# cek_pin_37.net
KiCad netlist of a schematic drawn in EAGLE
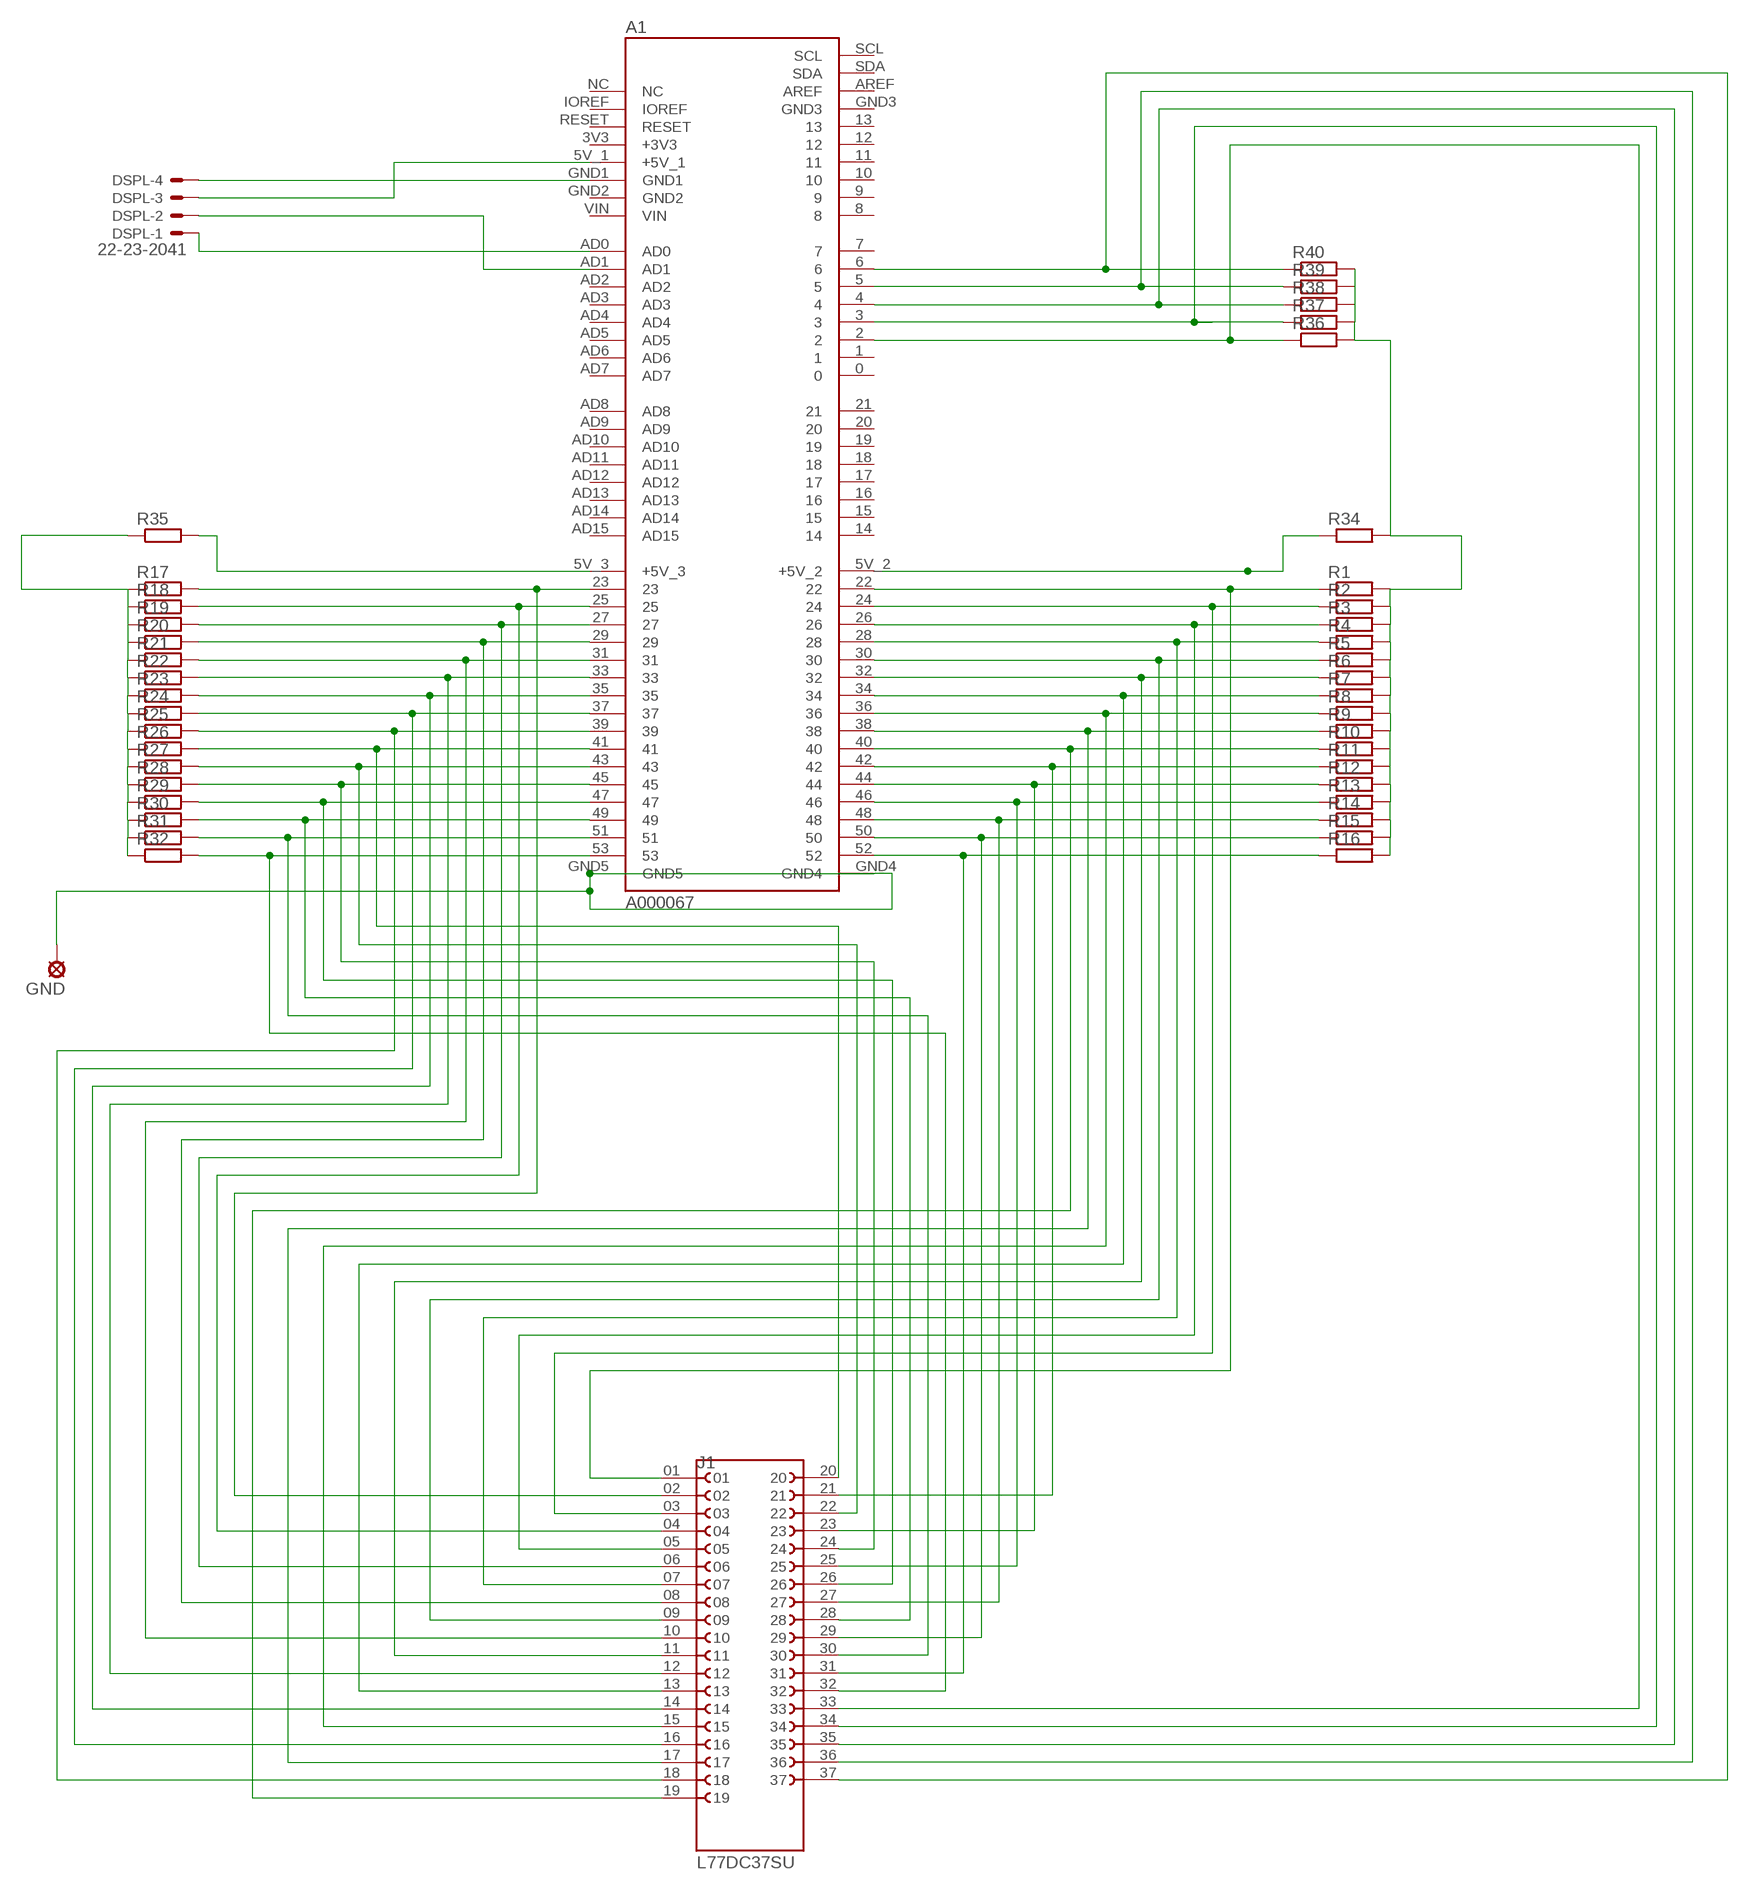
[diagram p0: schematic, sheet 1]

(export (version "E")
  (design (tool "Eeschema 10.0.6"))
  (components
    (comp (ref "A1")
      (value "A000067")
      (footprint "eagle-import:ARDUINO_A000067")
      (fields (field (name "MF") "Arduino") (field (name "MP") "Arduino Mega 2560 Rev3"))
      (libsource (lib "eagle-import") (part "A000067"))
    )
    (comp (ref "DSPL")
      (value "22-23-2041")
      (footprint "eagle-import:22-23-2041")
      (fields (field (name "MF") "MOLEX"))
      (libsource (lib "eagle-import") (part "22-23-2041"))
    )
    (comp (ref "GND")
      (value "LSP10")
      (footprint "eagle-import:LSP10")
      (libsource (lib "eagle-import") (part "LSP10"))
    )
    (comp (ref "J1")
      (value "L77DC37SU")
      (footprint "eagle-import:AMPHENOL_L77DC37SU")
      (fields (field (name "MF") "Amphenol Commercial Products") (field (name "MP") "L77-DC37S-U"))
      (libsource (lib "eagle-import") (part "L77DC37SU"))
    )
    (comp (ref "R1")
      (value "R-EU_0207/12")
      (footprint "eagle-import:0207_12")
      (libsource (lib "eagle-import") (part "R-EU_0207/12"))
    )
    (comp (ref "R2")
      (value "R-EU_0207/12")
      (footprint "eagle-import:0207_12")
      (libsource (lib "eagle-import") (part "R-EU_0207/12"))
    )
    (comp (ref "R3")
      (value "R-EU_0207/12")
      (footprint "eagle-import:0207_12")
      (libsource (lib "eagle-import") (part "R-EU_0207/12"))
    )
    (comp (ref "R4")
      (value "R-EU_0207/12")
      (footprint "eagle-import:0207_12")
      (libsource (lib "eagle-import") (part "R-EU_0207/12"))
    )
    (comp (ref "R5")
      (value "R-EU_0207/12")
      (footprint "eagle-import:0207_12")
      (libsource (lib "eagle-import") (part "R-EU_0207/12"))
    )
    (comp (ref "R6")
      (value "R-EU_0207/12")
      (footprint "eagle-import:0207_12")
      (libsource (lib "eagle-import") (part "R-EU_0207/12"))
    )
    (comp (ref "R7")
      (value "R-EU_0207/12")
      (footprint "eagle-import:0207_12")
      (libsource (lib "eagle-import") (part "R-EU_0207/12"))
    )
    (comp (ref "R8")
      (value "R-EU_0207/12")
      (footprint "eagle-import:0207_12")
      (libsource (lib "eagle-import") (part "R-EU_0207/12"))
    )
    (comp (ref "R9")
      (value "R-EU_0207/12")
      (footprint "eagle-import:0207_12")
      (libsource (lib "eagle-import") (part "R-EU_0207/12"))
    )
    (comp (ref "R10")
      (value "R-EU_0207/12")
      (footprint "eagle-import:0207_12")
      (libsource (lib "eagle-import") (part "R-EU_0207/12"))
    )
    (comp (ref "R11")
      (value "R-EU_0207/12")
      (footprint "eagle-import:0207_12")
      (libsource (lib "eagle-import") (part "R-EU_0207/12"))
    )
    (comp (ref "R12")
      (value "R-EU_0207/12")
      (footprint "eagle-import:0207_12")
      (libsource (lib "eagle-import") (part "R-EU_0207/12"))
    )
    (comp (ref "R13")
      (value "R-EU_0207/12")
      (footprint "eagle-import:0207_12")
      (libsource (lib "eagle-import") (part "R-EU_0207/12"))
    )
    (comp (ref "R14")
      (value "R-EU_0207/12")
      (footprint "eagle-import:0207_12")
      (libsource (lib "eagle-import") (part "R-EU_0207/12"))
    )
    (comp (ref "R15")
      (value "R-EU_0207/12")
      (footprint "eagle-import:0207_12")
      (libsource (lib "eagle-import") (part "R-EU_0207/12"))
    )
    (comp (ref "R16")
      (value "R-EU_0207/12")
      (footprint "eagle-import:0207_12")
      (libsource (lib "eagle-import") (part "R-EU_0207/12"))
    )
    (comp (ref "R17")
      (value "R-EU_0207/12")
      (footprint "eagle-import:0207_12")
      (libsource (lib "eagle-import") (part "R-EU_0207/12"))
    )
    (comp (ref "R18")
      (value "R-EU_0207/12")
      (footprint "eagle-import:0207_12")
      (libsource (lib "eagle-import") (part "R-EU_0207/12"))
    )
    (comp (ref "R19")
      (value "R-EU_0207/12")
      (footprint "eagle-import:0207_12")
      (libsource (lib "eagle-import") (part "R-EU_0207/12"))
    )
    (comp (ref "R20")
      (value "R-EU_0207/12")
      (footprint "eagle-import:0207_12")
      (libsource (lib "eagle-import") (part "R-EU_0207/12"))
    )
    (comp (ref "R21")
      (value "R-EU_0207/12")
      (footprint "eagle-import:0207_12")
      (libsource (lib "eagle-import") (part "R-EU_0207/12"))
    )
    (comp (ref "R22")
      (value "R-EU_0207/12")
      (footprint "eagle-import:0207_12")
      (libsource (lib "eagle-import") (part "R-EU_0207/12"))
    )
    (comp (ref "R23")
      (value "R-EU_0207/12")
      (footprint "eagle-import:0207_12")
      (libsource (lib "eagle-import") (part "R-EU_0207/12"))
    )
    (comp (ref "R24")
      (value "R-EU_0207/12")
      (footprint "eagle-import:0207_12")
      (libsource (lib "eagle-import") (part "R-EU_0207/12"))
    )
    (comp (ref "R25")
      (value "R-EU_0207/12")
      (footprint "eagle-import:0207_12")
      (libsource (lib "eagle-import") (part "R-EU_0207/12"))
    )
    (comp (ref "R26")
      (value "R-EU_0207/12")
      (footprint "eagle-import:0207_12")
      (libsource (lib "eagle-import") (part "R-EU_0207/12"))
    )
    (comp (ref "R27")
      (value "R-EU_0207/12")
      (footprint "eagle-import:0207_12")
      (libsource (lib "eagle-import") (part "R-EU_0207/12"))
    )
    (comp (ref "R28")
      (value "R-EU_0207/12")
      (footprint "eagle-import:0207_12")
      (libsource (lib "eagle-import") (part "R-EU_0207/12"))
    )
    (comp (ref "R29")
      (value "R-EU_0207/12")
      (footprint "eagle-import:0207_12")
      (libsource (lib "eagle-import") (part "R-EU_0207/12"))
    )
    (comp (ref "R30")
      (value "R-EU_0207/12")
      (footprint "eagle-import:0207_12")
      (libsource (lib "eagle-import") (part "R-EU_0207/12"))
    )
    (comp (ref "R31")
      (value "R-EU_0207/12")
      (footprint "eagle-import:0207_12")
      (libsource (lib "eagle-import") (part "R-EU_0207/12"))
    )
    (comp (ref "R32")
      (value "R-EU_0207/12")
      (footprint "eagle-import:0207_12")
      (libsource (lib "eagle-import") (part "R-EU_0207/12"))
    )
    (comp (ref "R34")
      (value "R-EU_0207/12")
      (footprint "eagle-import:0207_12")
      (libsource (lib "eagle-import") (part "R-EU_0207/12"))
    )
    (comp (ref "R35")
      (value "R-EU_0207/12")
      (footprint "eagle-import:0207_12")
      (libsource (lib "eagle-import") (part "R-EU_0207/12"))
    )
    (comp (ref "R36")
      (value "R-EU_0207/12")
      (footprint "eagle-import:0207_12")
      (libsource (lib "eagle-import") (part "R-EU_0207/12"))
    )
    (comp (ref "R37")
      (value "R-EU_0207/12")
      (footprint "eagle-import:0207_12")
      (libsource (lib "eagle-import") (part "R-EU_0207/12"))
    )
    (comp (ref "R38")
      (value "R-EU_0207/12")
      (footprint "eagle-import:0207_12")
      (libsource (lib "eagle-import") (part "R-EU_0207/12"))
    )
    (comp (ref "R39")
      (value "R-EU_0207/12")
      (footprint "eagle-import:0207_12")
      (libsource (lib "eagle-import") (part "R-EU_0207/12"))
    )
    (comp (ref "R40")
      (value "R-EU_0207/12")
      (footprint "eagle-import:0207_12")
      (libsource (lib "eagle-import") (part "R-EU_0207/12"))
    )
  )
  (nets
    (net (code "1") (name "Net-(A1-+5V_1)") (class "Default")
      (node (ref "A1") (pin "5V_1") (pinfunction "+5V_1_5V_1") (pintype "passive"))
      (node (ref "DSPL") (pin "3") (pinfunction "S_3") (pintype "passive"))
    )
    (net (code "2") (name "Net-(A1-+5V_2)") (class "Default")
      (node (ref "A1") (pin "5V_2") (pinfunction "+5V_2_5V_2") (pintype "passive"))
      (node (ref "R34") (pin "1") (pinfunction "1_1") (pintype "passive"))
    )
    (net (code "3") (name "Net-(A1-+5V_3)") (class "Default")
      (node (ref "A1") (pin "5V_3") (pinfunction "+5V_3_5V_3") (pintype "passive"))
      (node (ref "R35") (pin "2") (pinfunction "2_2") (pintype "passive"))
    )
    (net (code "4") (name "Net-(A1-Pad2)") (class "Default")
      (node (ref "A1") (pin "2") (pinfunction "2_2") (pintype "passive"))
      (node (ref "J1") (pin "33") (pinfunction "33_33") (pintype "passive"))
      (node (ref "R36") (pin "1") (pinfunction "1_1") (pintype "passive"))
    )
    (net (code "5") (name "Net-(A1-Pad3)") (class "Default")
      (node (ref "A1") (pin "3") (pinfunction "3_3") (pintype "passive"))
      (node (ref "J1") (pin "34") (pinfunction "34_34") (pintype "passive"))
      (node (ref "R37") (pin "1") (pinfunction "1_1") (pintype "passive"))
    )
    (net (code "6") (name "Net-(A1-Pad4)") (class "Default")
      (node (ref "A1") (pin "4") (pinfunction "4_4") (pintype "passive"))
      (node (ref "J1") (pin "35") (pinfunction "35_35") (pintype "passive"))
      (node (ref "R38") (pin "1") (pinfunction "1_1") (pintype "passive"))
    )
    (net (code "7") (name "Net-(A1-Pad5)") (class "Default")
      (node (ref "A1") (pin "5") (pinfunction "5_5") (pintype "passive"))
      (node (ref "J1") (pin "36") (pinfunction "36_36") (pintype "passive"))
      (node (ref "R39") (pin "1") (pinfunction "1_1") (pintype "passive"))
    )
    (net (code "8") (name "Net-(A1-Pad6)") (class "Default")
      (node (ref "A1") (pin "6") (pinfunction "6_6") (pintype "passive"))
      (node (ref "J1") (pin "37") (pinfunction "37_37") (pintype "passive"))
      (node (ref "R40") (pin "1") (pinfunction "1_1") (pintype "passive"))
    )
    (net (code "9") (name "Net-(A1-Pad22)") (class "Default")
      (node (ref "A1") (pin "22") (pinfunction "22_22") (pintype "passive"))
      (node (ref "J1") (pin "01") (pinfunction "01_01") (pintype "passive"))
      (node (ref "R1") (pin "1") (pinfunction "1_1") (pintype "passive"))
    )
    (net (code "10") (name "Net-(A1-Pad23)") (class "Default")
      (node (ref "A1") (pin "23") (pinfunction "23_23") (pintype "passive"))
      (node (ref "J1") (pin "02") (pinfunction "02_02") (pintype "passive"))
      (node (ref "R17") (pin "2") (pinfunction "2_2") (pintype "passive"))
    )
    (net (code "11") (name "Net-(A1-Pad24)") (class "Default")
      (node (ref "A1") (pin "24") (pinfunction "24_24") (pintype "passive"))
      (node (ref "J1") (pin "03") (pinfunction "03_03") (pintype "passive"))
      (node (ref "R2") (pin "1") (pinfunction "1_1") (pintype "passive"))
    )
    (net (code "12") (name "Net-(A1-Pad25)") (class "Default")
      (node (ref "A1") (pin "25") (pinfunction "25_25") (pintype "passive"))
      (node (ref "J1") (pin "04") (pinfunction "04_04") (pintype "passive"))
      (node (ref "R18") (pin "2") (pinfunction "2_2") (pintype "passive"))
    )
    (net (code "13") (name "Net-(A1-Pad26)") (class "Default")
      (node (ref "A1") (pin "26") (pinfunction "26_26") (pintype "passive"))
      (node (ref "J1") (pin "05") (pinfunction "05_05") (pintype "passive"))
      (node (ref "R3") (pin "1") (pinfunction "1_1") (pintype "passive"))
    )
    (net (code "14") (name "Net-(A1-Pad27)") (class "Default")
      (node (ref "A1") (pin "27") (pinfunction "27_27") (pintype "passive"))
      (node (ref "J1") (pin "06") (pinfunction "06_06") (pintype "passive"))
      (node (ref "R19") (pin "2") (pinfunction "2_2") (pintype "passive"))
    )
    (net (code "15") (name "Net-(A1-Pad28)") (class "Default")
      (node (ref "A1") (pin "28") (pinfunction "28_28") (pintype "passive"))
      (node (ref "J1") (pin "07") (pinfunction "07_07") (pintype "passive"))
      (node (ref "R4") (pin "1") (pinfunction "1_1") (pintype "passive"))
    )
    (net (code "16") (name "Net-(A1-Pad29)") (class "Default")
      (node (ref "A1") (pin "29") (pinfunction "29_29") (pintype "passive"))
      (node (ref "J1") (pin "08") (pinfunction "08_08") (pintype "passive"))
      (node (ref "R20") (pin "2") (pinfunction "2_2") (pintype "passive"))
    )
    (net (code "17") (name "Net-(A1-Pad30)") (class "Default")
      (node (ref "A1") (pin "30") (pinfunction "30_30") (pintype "passive"))
      (node (ref "J1") (pin "09") (pinfunction "09_09") (pintype "passive"))
      (node (ref "R5") (pin "1") (pinfunction "1_1") (pintype "passive"))
    )
    (net (code "18") (name "Net-(A1-Pad31)") (class "Default")
      (node (ref "A1") (pin "31") (pinfunction "31_31") (pintype "passive"))
      (node (ref "J1") (pin "10") (pinfunction "10_10") (pintype "passive"))
      (node (ref "R21") (pin "2") (pinfunction "2_2") (pintype "passive"))
    )
    (net (code "19") (name "Net-(A1-Pad32)") (class "Default")
      (node (ref "A1") (pin "32") (pinfunction "32_32") (pintype "passive"))
      (node (ref "J1") (pin "11") (pinfunction "11_11") (pintype "passive"))
      (node (ref "R6") (pin "1") (pinfunction "1_1") (pintype "passive"))
    )
    (net (code "20") (name "Net-(A1-Pad33)") (class "Default")
      (node (ref "A1") (pin "33") (pinfunction "33_33") (pintype "passive"))
      (node (ref "J1") (pin "12") (pinfunction "12_12") (pintype "passive"))
      (node (ref "R22") (pin "2") (pinfunction "2_2") (pintype "passive"))
    )
    (net (code "21") (name "Net-(A1-Pad34)") (class "Default")
      (node (ref "A1") (pin "34") (pinfunction "34_34") (pintype "passive"))
      (node (ref "J1") (pin "13") (pinfunction "13_13") (pintype "passive"))
      (node (ref "R7") (pin "1") (pinfunction "1_1") (pintype "passive"))
    )
    (net (code "22") (name "Net-(A1-Pad35)") (class "Default")
      (node (ref "A1") (pin "35") (pinfunction "35_35") (pintype "passive"))
      (node (ref "J1") (pin "14") (pinfunction "14_14") (pintype "passive"))
      (node (ref "R23") (pin "2") (pinfunction "2_2") (pintype "passive"))
    )
    (net (code "23") (name "Net-(A1-Pad36)") (class "Default")
      (node (ref "A1") (pin "36") (pinfunction "36_36") (pintype "passive"))
      (node (ref "J1") (pin "15") (pinfunction "15_15") (pintype "passive"))
      (node (ref "R8") (pin "1") (pinfunction "1_1") (pintype "passive"))
    )
    (net (code "24") (name "Net-(A1-Pad37)") (class "Default")
      (node (ref "A1") (pin "37") (pinfunction "37_37") (pintype "passive"))
      (node (ref "J1") (pin "16") (pinfunction "16_16") (pintype "passive"))
      (node (ref "R24") (pin "2") (pinfunction "2_2") (pintype "passive"))
    )
    (net (code "25") (name "Net-(A1-Pad38)") (class "Default")
      (node (ref "A1") (pin "38") (pinfunction "38_38") (pintype "passive"))
      (node (ref "J1") (pin "17") (pinfunction "17_17") (pintype "passive"))
      (node (ref "R9") (pin "1") (pinfunction "1_1") (pintype "passive"))
    )
    (net (code "26") (name "Net-(A1-Pad39)") (class "Default")
      (node (ref "A1") (pin "39") (pinfunction "39_39") (pintype "passive"))
      (node (ref "J1") (pin "18") (pinfunction "18_18") (pintype "passive"))
      (node (ref "R25") (pin "2") (pinfunction "2_2") (pintype "passive"))
    )
    (net (code "27") (name "Net-(A1-Pad40)") (class "Default")
      (node (ref "A1") (pin "40") (pinfunction "40_40") (pintype "passive"))
      (node (ref "J1") (pin "19") (pinfunction "19_19") (pintype "passive"))
      (node (ref "R10") (pin "1") (pinfunction "1_1") (pintype "passive"))
    )
    (net (code "28") (name "Net-(A1-Pad41)") (class "Default")
      (node (ref "A1") (pin "41") (pinfunction "41_41") (pintype "passive"))
      (node (ref "J1") (pin "20") (pinfunction "20_20") (pintype "passive"))
      (node (ref "R26") (pin "2") (pinfunction "2_2") (pintype "passive"))
    )
    (net (code "29") (name "Net-(A1-Pad42)") (class "Default")
      (node (ref "A1") (pin "42") (pinfunction "42_42") (pintype "passive"))
      (node (ref "J1") (pin "21") (pinfunction "21_21") (pintype "passive"))
      (node (ref "R11") (pin "1") (pinfunction "1_1") (pintype "passive"))
    )
    (net (code "30") (name "Net-(A1-Pad43)") (class "Default")
      (node (ref "A1") (pin "43") (pinfunction "43_43") (pintype "passive"))
      (node (ref "J1") (pin "22") (pinfunction "22_22") (pintype "passive"))
      (node (ref "R27") (pin "2") (pinfunction "2_2") (pintype "passive"))
    )
    (net (code "31") (name "Net-(A1-Pad44)") (class "Default")
      (node (ref "A1") (pin "44") (pinfunction "44_44") (pintype "passive"))
      (node (ref "J1") (pin "23") (pinfunction "23_23") (pintype "passive"))
      (node (ref "R12") (pin "1") (pinfunction "1_1") (pintype "passive"))
    )
    (net (code "32") (name "Net-(A1-Pad45)") (class "Default")
      (node (ref "A1") (pin "45") (pinfunction "45_45") (pintype "passive"))
      (node (ref "J1") (pin "24") (pinfunction "24_24") (pintype "passive"))
      (node (ref "R28") (pin "2") (pinfunction "2_2") (pintype "passive"))
    )
    (net (code "33") (name "Net-(A1-Pad46)") (class "Default")
      (node (ref "A1") (pin "46") (pinfunction "46_46") (pintype "passive"))
      (node (ref "J1") (pin "25") (pinfunction "25_25") (pintype "passive"))
      (node (ref "R13") (pin "1") (pinfunction "1_1") (pintype "passive"))
    )
    (net (code "34") (name "Net-(A1-Pad47)") (class "Default")
      (node (ref "A1") (pin "47") (pinfunction "47_47") (pintype "passive"))
      (node (ref "J1") (pin "26") (pinfunction "26_26") (pintype "passive"))
      (node (ref "R29") (pin "2") (pinfunction "2_2") (pintype "passive"))
    )
    (net (code "35") (name "Net-(A1-Pad48)") (class "Default")
      (node (ref "A1") (pin "48") (pinfunction "48_48") (pintype "passive"))
      (node (ref "J1") (pin "27") (pinfunction "27_27") (pintype "passive"))
      (node (ref "R14") (pin "1") (pinfunction "1_1") (pintype "passive"))
    )
    (net (code "36") (name "Net-(A1-Pad49)") (class "Default")
      (node (ref "A1") (pin "49") (pinfunction "49_49") (pintype "passive"))
      (node (ref "J1") (pin "28") (pinfunction "28_28") (pintype "passive"))
      (node (ref "R30") (pin "2") (pinfunction "2_2") (pintype "passive"))
    )
    (net (code "37") (name "Net-(A1-Pad50)") (class "Default")
      (node (ref "A1") (pin "50") (pinfunction "50_50") (pintype "passive"))
      (node (ref "J1") (pin "29") (pinfunction "29_29") (pintype "passive"))
      (node (ref "R15") (pin "1") (pinfunction "1_1") (pintype "passive"))
    )
    (net (code "38") (name "Net-(A1-Pad51)") (class "Default")
      (node (ref "A1") (pin "51") (pinfunction "51_51") (pintype "passive"))
      (node (ref "J1") (pin "30") (pinfunction "30_30") (pintype "passive"))
      (node (ref "R31") (pin "2") (pinfunction "2_2") (pintype "passive"))
    )
    (net (code "39") (name "Net-(A1-Pad52)") (class "Default")
      (node (ref "A1") (pin "52") (pinfunction "52_52") (pintype "passive"))
      (node (ref "J1") (pin "31") (pinfunction "31_31") (pintype "passive"))
      (node (ref "R16") (pin "1") (pinfunction "1_1") (pintype "passive"))
    )
    (net (code "40") (name "Net-(A1-Pad53)") (class "Default")
      (node (ref "A1") (pin "53") (pinfunction "53_53") (pintype "passive"))
      (node (ref "J1") (pin "32") (pinfunction "32_32") (pintype "passive"))
      (node (ref "R32") (pin "2") (pinfunction "2_2") (pintype "passive"))
    )
    (net (code "41") (name "Net-(A1-PadGND4)") (class "Default")
      (node (ref "A1") (pin "GND4") (pinfunction "GND4_GND4") (pintype "passive"))
      (node (ref "A1") (pin "GND5") (pinfunction "GND5_GND5") (pintype "passive"))
      (node (ref "GND") (pin "MP") (pinfunction "MP_MP") (pintype "passive"))
    )
    (net (code "42") (name "Net-(DSPLA-S)") (class "Default")
      (node (ref "A1") (pin "AD0") (pinfunction "AD0_AD0") (pintype "passive"))
      (node (ref "DSPL") (pin "1") (pinfunction "S_1") (pintype "passive"))
    )
    (net (code "43") (name "Net-(DSPLB-S)") (class "Default")
      (node (ref "A1") (pin "AD1") (pinfunction "AD1_AD1") (pintype "passive"))
      (node (ref "DSPL") (pin "2") (pinfunction "S_2") (pintype "passive"))
    )
    (net (code "44") (name "Net-(DSPLD-S)") (class "Default")
      (node (ref "A1") (pin "GND1") (pinfunction "GND1_GND1") (pintype "passive"))
      (node (ref "DSPL") (pin "4") (pinfunction "S_4") (pintype "passive"))
    )
    (net (code "45") (name "Net-(R1-Pad2)") (class "Default")
      (node (ref "R1") (pin "2") (pinfunction "2_2") (pintype "passive"))
      (node (ref "R10") (pin "2") (pinfunction "2_2") (pintype "passive"))
      (node (ref "R11") (pin "2") (pinfunction "2_2") (pintype "passive"))
      (node (ref "R12") (pin "2") (pinfunction "2_2") (pintype "passive"))
      (node (ref "R13") (pin "2") (pinfunction "2_2") (pintype "passive"))
      (node (ref "R14") (pin "2") (pinfunction "2_2") (pintype "passive"))
      (node (ref "R15") (pin "2") (pinfunction "2_2") (pintype "passive"))
      (node (ref "R16") (pin "2") (pinfunction "2_2") (pintype "passive"))
      (node (ref "R2") (pin "2") (pinfunction "2_2") (pintype "passive"))
      (node (ref "R3") (pin "2") (pinfunction "2_2") (pintype "passive"))
      (node (ref "R34") (pin "2") (pinfunction "2_2") (pintype "passive"))
      (node (ref "R36") (pin "2") (pinfunction "2_2") (pintype "passive"))
      (node (ref "R37") (pin "2") (pinfunction "2_2") (pintype "passive"))
      (node (ref "R38") (pin "2") (pinfunction "2_2") (pintype "passive"))
      (node (ref "R39") (pin "2") (pinfunction "2_2") (pintype "passive"))
      (node (ref "R4") (pin "2") (pinfunction "2_2") (pintype "passive"))
      (node (ref "R40") (pin "2") (pinfunction "2_2") (pintype "passive"))
      (node (ref "R5") (pin "2") (pinfunction "2_2") (pintype "passive"))
      (node (ref "R6") (pin "2") (pinfunction "2_2") (pintype "passive"))
      (node (ref "R7") (pin "2") (pinfunction "2_2") (pintype "passive"))
      (node (ref "R8") (pin "2") (pinfunction "2_2") (pintype "passive"))
      (node (ref "R9") (pin "2") (pinfunction "2_2") (pintype "passive"))
    )
    (net (code "46") (name "Net-(R17-Pad1)") (class "Default")
      (node (ref "R17") (pin "1") (pinfunction "1_1") (pintype "passive"))
      (node (ref "R18") (pin "1") (pinfunction "1_1") (pintype "passive"))
      (node (ref "R19") (pin "1") (pinfunction "1_1") (pintype "passive"))
      (node (ref "R20") (pin "1") (pinfunction "1_1") (pintype "passive"))
      (node (ref "R21") (pin "1") (pinfunction "1_1") (pintype "passive"))
      (node (ref "R22") (pin "1") (pinfunction "1_1") (pintype "passive"))
      (node (ref "R23") (pin "1") (pinfunction "1_1") (pintype "passive"))
      (node (ref "R24") (pin "1") (pinfunction "1_1") (pintype "passive"))
      (node (ref "R25") (pin "1") (pinfunction "1_1") (pintype "passive"))
      (node (ref "R26") (pin "1") (pinfunction "1_1") (pintype "passive"))
      (node (ref "R27") (pin "1") (pinfunction "1_1") (pintype "passive"))
      (node (ref "R28") (pin "1") (pinfunction "1_1") (pintype "passive"))
      (node (ref "R29") (pin "1") (pinfunction "1_1") (pintype "passive"))
      (node (ref "R30") (pin "1") (pinfunction "1_1") (pintype "passive"))
      (node (ref "R31") (pin "1") (pinfunction "1_1") (pintype "passive"))
      (node (ref "R32") (pin "1") (pinfunction "1_1") (pintype "passive"))
      (node (ref "R35") (pin "1") (pinfunction "1_1") (pintype "passive"))
    )
    (net (code "47") (name "unconnected-(A1-+3V3-Pad3V3)") (class "Default")
      (node (ref "A1") (pin "3V3") (pinfunction "+3V3_3V3") (pintype "passive"))
    )
    (net (code "48") (name "unconnected-(A1-Pad0)") (class "Default")
      (node (ref "A1") (pin "0") (pinfunction "0_0") (pintype "passive"))
    )
    (net (code "49") (name "unconnected-(A1-Pad1)") (class "Default")
      (node (ref "A1") (pin "1") (pinfunction "1_1") (pintype "passive"))
    )
    (net (code "50") (name "unconnected-(A1-Pad7)") (class "Default")
      (node (ref "A1") (pin "7") (pinfunction "7_7") (pintype "passive"))
    )
    (net (code "51") (name "unconnected-(A1-Pad8)") (class "Default")
      (node (ref "A1") (pin "8") (pinfunction "8_8") (pintype "passive"))
    )
    (net (code "52") (name "unconnected-(A1-Pad9)") (class "Default")
      (node (ref "A1") (pin "9") (pinfunction "9_9") (pintype "passive"))
    )
    (net (code "53") (name "unconnected-(A1-Pad10)") (class "Default")
      (node (ref "A1") (pin "10") (pinfunction "10_10") (pintype "passive"))
    )
    (net (code "54") (name "unconnected-(A1-Pad11)") (class "Default")
      (node (ref "A1") (pin "11") (pinfunction "11_11") (pintype "passive"))
    )
    (net (code "55") (name "unconnected-(A1-Pad12)") (class "Default")
      (node (ref "A1") (pin "12") (pinfunction "12_12") (pintype "passive"))
    )
    (net (code "56") (name "unconnected-(A1-Pad13)") (class "Default")
      (node (ref "A1") (pin "13") (pinfunction "13_13") (pintype "passive"))
    )
    (net (code "57") (name "unconnected-(A1-Pad14)") (class "Default")
      (node (ref "A1") (pin "14") (pinfunction "14_14") (pintype "passive"))
    )
    (net (code "58") (name "unconnected-(A1-Pad15)") (class "Default")
      (node (ref "A1") (pin "15") (pinfunction "15_15") (pintype "passive"))
    )
    (net (code "59") (name "unconnected-(A1-Pad16)") (class "Default")
      (node (ref "A1") (pin "16") (pinfunction "16_16") (pintype "passive"))
    )
    (net (code "60") (name "unconnected-(A1-Pad17)") (class "Default")
      (node (ref "A1") (pin "17") (pinfunction "17_17") (pintype "passive"))
    )
    (net (code "61") (name "unconnected-(A1-Pad18)") (class "Default")
      (node (ref "A1") (pin "18") (pinfunction "18_18") (pintype "passive"))
    )
    (net (code "62") (name "unconnected-(A1-Pad19)") (class "Default")
      (node (ref "A1") (pin "19") (pinfunction "19_19") (pintype "passive"))
    )
    (net (code "63") (name "unconnected-(A1-Pad20)") (class "Default")
      (node (ref "A1") (pin "20") (pinfunction "20_20") (pintype "passive"))
    )
    (net (code "64") (name "unconnected-(A1-Pad21)") (class "Default")
      (node (ref "A1") (pin "21") (pinfunction "21_21") (pintype "passive"))
    )
    (net (code "65") (name "unconnected-(A1-PadAD2)") (class "Default")
      (node (ref "A1") (pin "AD2") (pinfunction "AD2_AD2") (pintype "passive"))
    )
    (net (code "66") (name "unconnected-(A1-PadAD3)") (class "Default")
      (node (ref "A1") (pin "AD3") (pinfunction "AD3_AD3") (pintype "passive"))
    )
    (net (code "67") (name "unconnected-(A1-PadAD4)") (class "Default")
      (node (ref "A1") (pin "AD4") (pinfunction "AD4_AD4") (pintype "passive"))
    )
    (net (code "68") (name "unconnected-(A1-PadAD5)") (class "Default")
      (node (ref "A1") (pin "AD5") (pinfunction "AD5_AD5") (pintype "passive"))
    )
    (net (code "69") (name "unconnected-(A1-PadAD6)") (class "Default")
      (node (ref "A1") (pin "AD6") (pinfunction "AD6_AD6") (pintype "passive"))
    )
    (net (code "70") (name "unconnected-(A1-PadAD7)") (class "Default")
      (node (ref "A1") (pin "AD7") (pinfunction "AD7_AD7") (pintype "passive"))
    )
    (net (code "71") (name "unconnected-(A1-PadAD8)") (class "Default")
      (node (ref "A1") (pin "AD8") (pinfunction "AD8_AD8") (pintype "passive"))
    )
    (net (code "72") (name "unconnected-(A1-PadAD9)") (class "Default")
      (node (ref "A1") (pin "AD9") (pinfunction "AD9_AD9") (pintype "passive"))
    )
    (net (code "73") (name "unconnected-(A1-PadAD10)") (class "Default")
      (node (ref "A1") (pin "AD10") (pinfunction "AD10_AD10") (pintype "passive"))
    )
    (net (code "74") (name "unconnected-(A1-PadAD11)") (class "Default")
      (node (ref "A1") (pin "AD11") (pinfunction "AD11_AD11") (pintype "passive"))
    )
    (net (code "75") (name "unconnected-(A1-PadAD12)") (class "Default")
      (node (ref "A1") (pin "AD12") (pinfunction "AD12_AD12") (pintype "passive"))
    )
    (net (code "76") (name "unconnected-(A1-PadAD13)") (class "Default")
      (node (ref "A1") (pin "AD13") (pinfunction "AD13_AD13") (pintype "passive"))
    )
    (net (code "77") (name "unconnected-(A1-PadAD14)") (class "Default")
      (node (ref "A1") (pin "AD14") (pinfunction "AD14_AD14") (pintype "passive"))
    )
    (net (code "78") (name "unconnected-(A1-PadAD15)") (class "Default")
      (node (ref "A1") (pin "AD15") (pinfunction "AD15_AD15") (pintype "passive"))
    )
    (net (code "79") (name "unconnected-(A1-PadAREF)") (class "Default")
      (node (ref "A1") (pin "AREF") (pinfunction "AREF_AREF") (pintype "passive"))
    )
    (net (code "80") (name "unconnected-(A1-PadGND2)") (class "Default")
      (node (ref "A1") (pin "GND2") (pinfunction "GND2_GND2") (pintype "passive"))
    )
    (net (code "81") (name "unconnected-(A1-PadGND3)") (class "Default")
      (node (ref "A1") (pin "GND3") (pinfunction "GND3_GND3") (pintype "passive"))
    )
    (net (code "82") (name "unconnected-(A1-PadIOREF)") (class "Default")
      (node (ref "A1") (pin "IOREF") (pinfunction "IOREF_IOREF") (pintype "passive"))
    )
    (net (code "83") (name "unconnected-(A1-PadNC)") (class "Default")
      (node (ref "A1") (pin "NC") (pinfunction "NC_NC") (pintype "passive"))
    )
    (net (code "84") (name "unconnected-(A1-PadRESET)") (class "Default")
      (node (ref "A1") (pin "RESET") (pinfunction "RESET_RESET") (pintype "passive"))
    )
    (net (code "85") (name "unconnected-(A1-PadSCL)") (class "Default")
      (node (ref "A1") (pin "SCL") (pinfunction "SCL_SCL") (pintype "passive"))
    )
    (net (code "86") (name "unconnected-(A1-PadSDA)") (class "Default")
      (node (ref "A1") (pin "SDA") (pinfunction "SDA_SDA") (pintype "passive"))
    )
    (net (code "87") (name "unconnected-(A1-PadVIN)") (class "Default")
      (node (ref "A1") (pin "VIN") (pinfunction "VIN_VIN") (pintype "passive"))
    )
  )
)
